# PROCESSOR_MEMORIES.net
KiCad netlist of a schematic drawn in Altium Designer
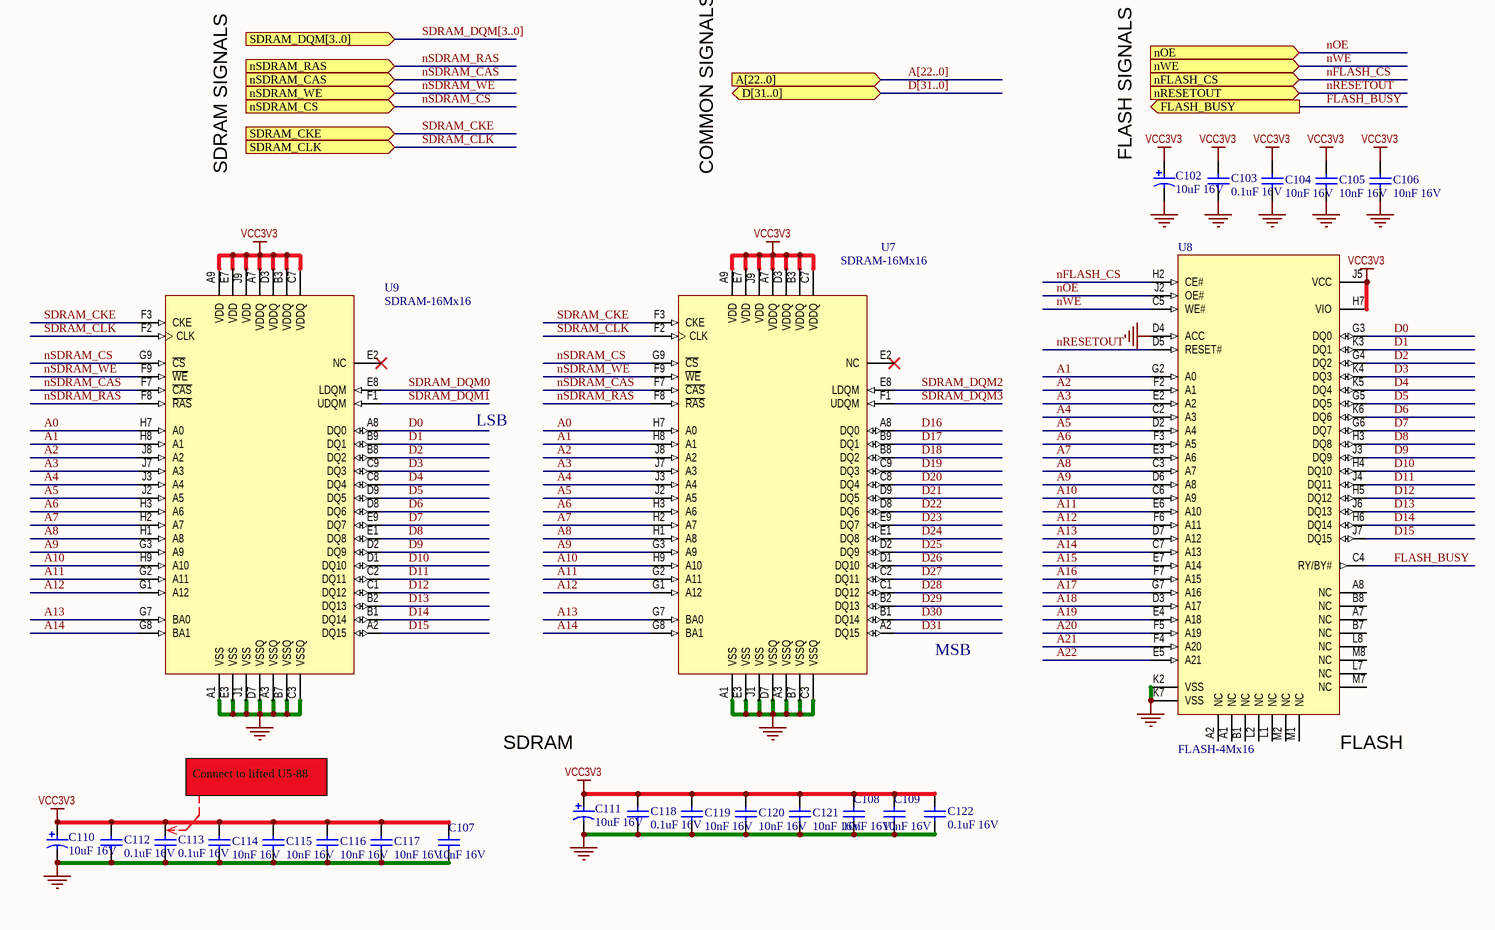
[diagram p0: PROCESSOR_MEMORIES.SchDoc]

(export (version "E")
  (design (tool "Eeschema 10.0.6"))
  (components
    (comp (ref "C102")
      (value "10uF 16V")
      (footprint "CAPC3528")
      (description "Polar Capacitor")
      (libsource (lib "Altium Design Library") (part "CAP-P"))
    )
    (comp (ref "C103")
      (value "0.1uF 16V")
      (footprint "CAPC1005")
      (description "Capacitor")
      (libsource (lib "Altium Design Library") (part "CAP-NP"))
    )
    (comp (ref "C104")
      (value "10nF 16V")
      (footprint "CAPC1005")
      (description "Capacitor")
      (libsource (lib "Altium Design Library") (part "CAP-NP"))
    )
    (comp (ref "C105")
      (value "10nF 16V")
      (footprint "CAPC1005")
      (description "Capacitor")
      (libsource (lib "Altium Design Library") (part "CAP-NP"))
    )
    (comp (ref "C106")
      (value "10nF 16V")
      (footprint "CAPC1005")
      (description "Capacitor")
      (libsource (lib "Altium Design Library") (part "CAP-NP"))
    )
    (comp (ref "C107")
      (value "10nF 16V")
      (footprint "CAPC1005")
      (description "Capacitor")
      (libsource (lib "Altium Design Library") (part "CAP-NP"))
    )
    (comp (ref "C108")
      (value "10nF 16V")
      (footprint "CAPC1005")
      (description "Capacitor")
      (libsource (lib "Altium Design Library") (part "CAP-NP"))
    )
    (comp (ref "C109")
      (value "10nF 16V")
      (footprint "CAPC1005")
      (description "Capacitor")
      (libsource (lib "Altium Design Library") (part "CAP-NP"))
    )
    (comp (ref "C110")
      (value "10uF 16V")
      (footprint "CAPC3528")
      (description "Polar Capacitor")
      (libsource (lib "Altium Design Library") (part "CAP-P"))
    )
    (comp (ref "C111")
      (value "10uF 16V")
      (footprint "CAPC3528")
      (description "Polar Capacitor")
      (libsource (lib "Altium Design Library") (part "CAP-P"))
    )
    (comp (ref "C112")
      (value "0.1uF 16V")
      (footprint "CAPC1005")
      (description "Capacitor")
      (libsource (lib "Altium Design Library") (part "CAP-NP"))
    )
    (comp (ref "C113")
      (value "0.1uF 16V")
      (footprint "CAPC1005")
      (description "Capacitor")
      (libsource (lib "Altium Design Library") (part "CAP-NP"))
    )
    (comp (ref "C114")
      (value "10nF 16V")
      (footprint "CAPC1005")
      (description "Capacitor")
      (libsource (lib "Altium Design Library") (part "CAP-NP"))
    )
    (comp (ref "C115")
      (value "10nF 16V")
      (footprint "CAPC1005")
      (description "Capacitor")
      (libsource (lib "Altium Design Library") (part "CAP-NP"))
    )
    (comp (ref "C116")
      (value "10nF 16V")
      (footprint "CAPC1005")
      (description "Capacitor")
      (libsource (lib "Altium Design Library") (part "CAP-NP"))
    )
    (comp (ref "C117")
      (value "10nF 16V")
      (footprint "CAPC1005")
      (description "Capacitor")
      (libsource (lib "Altium Design Library") (part "CAP-NP"))
    )
    (comp (ref "C118")
      (value "0.1uF 16V")
      (footprint "CAPC1005")
      (description "Capacitor")
      (libsource (lib "Altium Design Library") (part "CAP-NP"))
    )
    (comp (ref "C119")
      (value "10nF 16V")
      (footprint "CAPC1005")
      (description "Capacitor")
      (libsource (lib "Altium Design Library") (part "CAP-NP"))
    )
    (comp (ref "C120")
      (value "10nF 16V")
      (footprint "CAPC1005")
      (description "Capacitor")
      (libsource (lib "Altium Design Library") (part "CAP-NP"))
    )
    (comp (ref "C121")
      (value "10nF 16V")
      (footprint "CAPC1005")
      (description "Capacitor")
      (libsource (lib "Altium Design Library") (part "CAP-NP"))
    )
    (comp (ref "C122")
      (value "0.1uF 16V")
      (footprint "CAPC1005")
      (description "Capacitor")
      (libsource (lib "Altium Design Library") (part "CAP-NP"))
    )
    (comp (ref "U7")
      (value "SDRAM-16Mx16")
      (footprint "BGA80P9X6-54")
      (description "256Mb Synchronous High-Speed CMOS DRAM, 16Mb x 16Bit x 4 Banks, 54-Ball FPGA, Commercial")
      (libsource (lib "Altium Design Library") (part "MT48LC16M16A2FG"))
    )
    (comp (ref "U8")
      (value "FLASH-4Mx16")
      (footprint "BGA80P12X8-63")
      (libsource (lib "Altium Design Library") (part "AM29LV640DU90RWHI"))
    )
    (comp (ref "U9")
      (value "SDRAM-16Mx16")
      (footprint "BGA80P9X6-54")
      (description "256Mb Synchronous High-Speed CMOS DRAM, 16Mb x 16Bit x 4 Banks, 54-Ball FPGA, Commercial")
      (libsource (lib "Altium Design Library") (part "MT48LC16M16A2FG"))
    )
  )
  (nets
    (net (code "1") (name "/A0") (class "Default")
      (node (ref "U7") (pin "H7") (pinfunction "A0_H7") (pintype "input"))
      (node (ref "U9") (pin "H7") (pinfunction "A0_H7") (pintype "input"))
    )
    (net (code "2") (name "/A1") (class "Default")
      (node (ref "U7") (pin "H8") (pinfunction "A1_H8") (pintype "input"))
      (node (ref "U8") (pin "G2") (pinfunction "A0_G2") (pintype "input"))
      (node (ref "U9") (pin "H8") (pinfunction "A1_H8") (pintype "input"))
    )
    (net (code "3") (name "/A2") (class "Default")
      (node (ref "U7") (pin "J8") (pinfunction "A2_J8") (pintype "input"))
      (node (ref "U8") (pin "F2") (pinfunction "A1_F2") (pintype "input"))
      (node (ref "U9") (pin "J8") (pinfunction "A2_J8") (pintype "input"))
    )
    (net (code "4") (name "/A3") (class "Default")
      (node (ref "U7") (pin "J7") (pinfunction "A3_J7") (pintype "input"))
      (node (ref "U8") (pin "E2") (pinfunction "A2_E2") (pintype "input"))
      (node (ref "U9") (pin "J7") (pinfunction "A3_J7") (pintype "input"))
    )
    (net (code "5") (name "/A4") (class "Default")
      (node (ref "U7") (pin "J3") (pinfunction "A4_J3") (pintype "input"))
      (node (ref "U8") (pin "C2") (pinfunction "A3_C2") (pintype "input"))
      (node (ref "U9") (pin "J3") (pinfunction "A4_J3") (pintype "input"))
    )
    (net (code "6") (name "/A5") (class "Default")
      (node (ref "U7") (pin "J2") (pinfunction "A5_J2") (pintype "input"))
      (node (ref "U8") (pin "D2") (pinfunction "A4_D2") (pintype "input"))
      (node (ref "U9") (pin "J2") (pinfunction "A5_J2") (pintype "input"))
    )
    (net (code "7") (name "/A6") (class "Default")
      (node (ref "U7") (pin "H3") (pinfunction "A6_H3") (pintype "input"))
      (node (ref "U8") (pin "F3") (pinfunction "A5_F3") (pintype "input"))
      (node (ref "U9") (pin "H3") (pinfunction "A6_H3") (pintype "input"))
    )
    (net (code "8") (name "/A7") (class "Default")
      (node (ref "U7") (pin "H2") (pinfunction "A7_H2") (pintype "input"))
      (node (ref "U8") (pin "E3") (pinfunction "A6_E3") (pintype "input"))
      (node (ref "U9") (pin "H2") (pinfunction "A7_H2") (pintype "input"))
    )
    (net (code "9") (name "/A8") (class "Default")
      (node (ref "U7") (pin "H1") (pinfunction "A8_H1") (pintype "input"))
      (node (ref "U8") (pin "C3") (pinfunction "A7_C3") (pintype "input"))
      (node (ref "U9") (pin "H1") (pinfunction "A8_H1") (pintype "input"))
    )
    (net (code "10") (name "/A9") (class "Default")
      (node (ref "U7") (pin "G3") (pinfunction "A9_G3") (pintype "input"))
      (node (ref "U8") (pin "D6") (pinfunction "A8_D6") (pintype "input"))
      (node (ref "U9") (pin "G3") (pinfunction "A9_G3") (pintype "input"))
    )
    (net (code "11") (name "/A10") (class "Default")
      (node (ref "U7") (pin "H9") (pinfunction "A10_H9") (pintype "input"))
      (node (ref "U8") (pin "C6") (pinfunction "A9_C6") (pintype "input"))
      (node (ref "U9") (pin "H9") (pinfunction "A10_H9") (pintype "input"))
    )
    (net (code "12") (name "/A11") (class "Default")
      (node (ref "U7") (pin "G2") (pinfunction "A11_G2") (pintype "input"))
      (node (ref "U8") (pin "E6") (pinfunction "A10_E6") (pintype "input"))
      (node (ref "U9") (pin "G2") (pinfunction "A11_G2") (pintype "input"))
    )
    (net (code "13") (name "/A12") (class "Default")
      (node (ref "U7") (pin "G1") (pinfunction "A12_G1") (pintype "input"))
      (node (ref "U8") (pin "F6") (pinfunction "A11_F6") (pintype "input"))
      (node (ref "U9") (pin "G1") (pinfunction "A12_G1") (pintype "input"))
    )
    (net (code "14") (name "/A13") (class "Default")
      (node (ref "U7") (pin "G7") (pinfunction "BA0_G7") (pintype "input"))
      (node (ref "U8") (pin "D7") (pinfunction "A12_D7") (pintype "input"))
      (node (ref "U9") (pin "G7") (pinfunction "BA0_G7") (pintype "input"))
    )
    (net (code "15") (name "/A14") (class "Default")
      (node (ref "U7") (pin "G8") (pinfunction "BA1_G8") (pintype "input"))
      (node (ref "U8") (pin "C7") (pinfunction "A13_C7") (pintype "input"))
      (node (ref "U9") (pin "G8") (pinfunction "BA1_G8") (pintype "input"))
    )
    (net (code "16") (name "/A15") (class "Default")
      (node (ref "U8") (pin "E7") (pinfunction "A14_E7") (pintype "input"))
    )
    (net (code "17") (name "/A16") (class "Default")
      (node (ref "U8") (pin "F7") (pinfunction "A15_F7") (pintype "input"))
    )
    (net (code "18") (name "/A17") (class "Default")
      (node (ref "U8") (pin "G7") (pinfunction "A16_G7") (pintype "input"))
    )
    (net (code "19") (name "/A18") (class "Default")
      (node (ref "U8") (pin "D3") (pinfunction "A17_D3") (pintype "input"))
    )
    (net (code "20") (name "/A19") (class "Default")
      (node (ref "U8") (pin "E4") (pinfunction "A18_E4") (pintype "input"))
    )
    (net (code "21") (name "/A20") (class "Default")
      (node (ref "U8") (pin "F5") (pinfunction "A19_F5") (pintype "input"))
    )
    (net (code "22") (name "/A21") (class "Default")
      (node (ref "U8") (pin "F4") (pinfunction "A20_F4") (pintype "input"))
    )
    (net (code "23") (name "/A22") (class "Default")
      (node (ref "U8") (pin "E5") (pinfunction "A21_E5") (pintype "input"))
    )
    (net (code "25") (name "/D0") (class "Default")
      (node (ref "U8") (pin "G3") (pinfunction "DQ0_G3") (pintype "bidirectional"))
      (node (ref "U9") (pin "A8") (pinfunction "DQ0_A8") (pintype "bidirectional"))
    )
    (net (code "26") (name "/D1") (class "Default")
      (node (ref "U8") (pin "K3") (pinfunction "DQ1_K3") (pintype "bidirectional"))
      (node (ref "U9") (pin "B9") (pinfunction "DQ1_B9") (pintype "bidirectional"))
    )
    (net (code "27") (name "/D2") (class "Default")
      (node (ref "U8") (pin "G4") (pinfunction "DQ2_G4") (pintype "bidirectional"))
      (node (ref "U9") (pin "B8") (pinfunction "DQ2_B8") (pintype "bidirectional"))
    )
    (net (code "28") (name "/D3") (class "Default")
      (node (ref "U8") (pin "K4") (pinfunction "DQ3_K4") (pintype "bidirectional"))
      (node (ref "U9") (pin "C9") (pinfunction "DQ3_C9") (pintype "bidirectional"))
    )
    (net (code "29") (name "/D4") (class "Default")
      (node (ref "U8") (pin "K5") (pinfunction "DQ4_K5") (pintype "bidirectional"))
      (node (ref "U9") (pin "C8") (pinfunction "DQ4_C8") (pintype "bidirectional"))
    )
    (net (code "30") (name "/D5") (class "Default")
      (node (ref "U8") (pin "G5") (pinfunction "DQ5_G5") (pintype "bidirectional"))
      (node (ref "U9") (pin "D9") (pinfunction "DQ5_D9") (pintype "bidirectional"))
    )
    (net (code "31") (name "/D6") (class "Default")
      (node (ref "U8") (pin "K6") (pinfunction "DQ6_K6") (pintype "bidirectional"))
      (node (ref "U9") (pin "D8") (pinfunction "DQ6_D8") (pintype "bidirectional"))
    )
    (net (code "32") (name "/D7") (class "Default")
      (node (ref "U8") (pin "G6") (pinfunction "DQ7_G6") (pintype "bidirectional"))
      (node (ref "U9") (pin "E9") (pinfunction "DQ7_E9") (pintype "bidirectional"))
    )
    (net (code "33") (name "/D8") (class "Default")
      (node (ref "U8") (pin "H3") (pinfunction "DQ8_H3") (pintype "bidirectional"))
      (node (ref "U9") (pin "E1") (pinfunction "DQ8_E1") (pintype "bidirectional"))
    )
    (net (code "34") (name "/D9") (class "Default")
      (node (ref "U8") (pin "J3") (pinfunction "DQ9_J3") (pintype "bidirectional"))
      (node (ref "U9") (pin "D2") (pinfunction "DQ9_D2") (pintype "bidirectional"))
    )
    (net (code "35") (name "/D10") (class "Default")
      (node (ref "U8") (pin "H4") (pinfunction "DQ10_H4") (pintype "bidirectional"))
      (node (ref "U9") (pin "D1") (pinfunction "DQ10_D1") (pintype "bidirectional"))
    )
    (net (code "36") (name "/D11") (class "Default")
      (node (ref "U8") (pin "J4") (pinfunction "DQ11_J4") (pintype "bidirectional"))
      (node (ref "U9") (pin "C2") (pinfunction "DQ11_C2") (pintype "bidirectional"))
    )
    (net (code "37") (name "/D12") (class "Default")
      (node (ref "U8") (pin "H5") (pinfunction "DQ12_H5") (pintype "bidirectional"))
      (node (ref "U9") (pin "C1") (pinfunction "DQ12_C1") (pintype "bidirectional"))
    )
    (net (code "38") (name "/D13") (class "Default")
      (node (ref "U8") (pin "J6") (pinfunction "DQ13_J6") (pintype "bidirectional"))
      (node (ref "U9") (pin "B2") (pinfunction "DQ13_B2") (pintype "bidirectional"))
    )
    (net (code "39") (name "/D14") (class "Default")
      (node (ref "U8") (pin "H6") (pinfunction "DQ14_H6") (pintype "bidirectional"))
      (node (ref "U9") (pin "B1") (pinfunction "DQ14_B1") (pintype "bidirectional"))
    )
    (net (code "40") (name "/D15") (class "Default")
      (node (ref "U8") (pin "J7") (pinfunction "DQ15_J7") (pintype "bidirectional"))
      (node (ref "U9") (pin "A2") (pinfunction "DQ15_A2") (pintype "bidirectional"))
    )
    (net (code "41") (name "/D16") (class "Default")
      (node (ref "U7") (pin "A8") (pinfunction "DQ0_A8") (pintype "bidirectional"))
    )
    (net (code "42") (name "/D17") (class "Default")
      (node (ref "U7") (pin "B9") (pinfunction "DQ1_B9") (pintype "bidirectional"))
    )
    (net (code "43") (name "/D18") (class "Default")
      (node (ref "U7") (pin "B8") (pinfunction "DQ2_B8") (pintype "bidirectional"))
    )
    (net (code "44") (name "/D19") (class "Default")
      (node (ref "U7") (pin "C9") (pinfunction "DQ3_C9") (pintype "bidirectional"))
    )
    (net (code "45") (name "/D20") (class "Default")
      (node (ref "U7") (pin "C8") (pinfunction "DQ4_C8") (pintype "bidirectional"))
    )
    (net (code "46") (name "/D21") (class "Default")
      (node (ref "U7") (pin "D9") (pinfunction "DQ5_D9") (pintype "bidirectional"))
    )
    (net (code "47") (name "/D22") (class "Default")
      (node (ref "U7") (pin "D8") (pinfunction "DQ6_D8") (pintype "bidirectional"))
    )
    (net (code "48") (name "/D23") (class "Default")
      (node (ref "U7") (pin "E9") (pinfunction "DQ7_E9") (pintype "bidirectional"))
    )
    (net (code "49") (name "/D24") (class "Default")
      (node (ref "U7") (pin "E1") (pinfunction "DQ8_E1") (pintype "bidirectional"))
    )
    (net (code "50") (name "/D25") (class "Default")
      (node (ref "U7") (pin "D2") (pinfunction "DQ9_D2") (pintype "bidirectional"))
    )
    (net (code "51") (name "/D26") (class "Default")
      (node (ref "U7") (pin "D1") (pinfunction "DQ10_D1") (pintype "bidirectional"))
    )
    (net (code "52") (name "/D27") (class "Default")
      (node (ref "U7") (pin "C2") (pinfunction "DQ11_C2") (pintype "bidirectional"))
    )
    (net (code "53") (name "/D28") (class "Default")
      (node (ref "U7") (pin "C1") (pinfunction "DQ12_C1") (pintype "bidirectional"))
    )
    (net (code "54") (name "/D29") (class "Default")
      (node (ref "U7") (pin "B2") (pinfunction "DQ13_B2") (pintype "bidirectional"))
    )
    (net (code "55") (name "/D30") (class "Default")
      (node (ref "U7") (pin "B1") (pinfunction "DQ14_B1") (pintype "bidirectional"))
    )
    (net (code "56") (name "/D31") (class "Default")
      (node (ref "U7") (pin "A2") (pinfunction "DQ15_A2") (pintype "bidirectional"))
    )
    (net (code "58") (name "/FLASH_BUSY") (class "Default")
      (node (ref "U8") (pin "C4") (pinfunction "RY/BY#_C4") (pintype "output"))
    )
    (net (code "59") (name "/SDRAM_CKE") (class "Default")
      (node (ref "U7") (pin "F3") (pinfunction "CKE_F3") (pintype "input"))
      (node (ref "U9") (pin "F3") (pinfunction "CKE_F3") (pintype "input"))
    )
    (net (code "60") (name "/SDRAM_CLK") (class "Default")
      (node (ref "U7") (pin "F2") (pinfunction "CLK_F2") (pintype "input"))
      (node (ref "U9") (pin "F2") (pinfunction "CLK_F2") (pintype "input"))
    )
    (net (code "61") (name "/SDRAM_DQM0") (class "Default")
      (node (ref "U9") (pin "E8") (pinfunction "LDQM_E8") (pintype "input"))
    )
    (net (code "62") (name "/SDRAM_DQM1") (class "Default")
      (node (ref "U9") (pin "F1") (pinfunction "UDQM_F1") (pintype "input"))
    )
    (net (code "63") (name "/SDRAM_DQM2") (class "Default")
      (node (ref "U7") (pin "E8") (pinfunction "LDQM_E8") (pintype "input"))
    )
    (net (code "64") (name "/SDRAM_DQM3") (class "Default")
      (node (ref "U7") (pin "F1") (pinfunction "UDQM_F1") (pintype "input"))
    )
    (net (code "66") (name "/nFLASH_CS") (class "Default")
      (node (ref "U8") (pin "H2") (pinfunction "CE#_H2") (pintype "input"))
    )
    (net (code "67") (name "/nOE") (class "Default")
      (node (ref "U8") (pin "J2") (pinfunction "OE#_J2") (pintype "input"))
    )
    (net (code "68") (name "/nRESETOUT") (class "Default")
      (node (ref "U8") (pin "D5") (pinfunction "RESET#_D5") (pintype "input"))
    )
    (net (code "69") (name "/nSDRAM_CAS") (class "Default")
      (node (ref "U7") (pin "F7") (pinfunction "~{CAS}_F7") (pintype "input"))
      (node (ref "U9") (pin "F7") (pinfunction "~{CAS}_F7") (pintype "input"))
    )
    (net (code "70") (name "/nSDRAM_CS") (class "Default")
      (node (ref "U7") (pin "G9") (pinfunction "~{CS}_G9") (pintype "input"))
      (node (ref "U9") (pin "G9") (pinfunction "~{CS}_G9") (pintype "input"))
    )
    (net (code "71") (name "/nSDRAM_RAS") (class "Default")
      (node (ref "U7") (pin "F8") (pinfunction "~{RAS}_F8") (pintype "input"))
      (node (ref "U9") (pin "F8") (pinfunction "~{RAS}_F8") (pintype "input"))
    )
    (net (code "72") (name "/nSDRAM_WE") (class "Default")
      (node (ref "U7") (pin "F9") (pinfunction "~{WE}_F9") (pintype "input"))
      (node (ref "U9") (pin "F9") (pinfunction "~{WE}_F9") (pintype "input"))
    )
    (net (code "73") (name "/nWE") (class "Default")
      (node (ref "U8") (pin "C5") (pinfunction "WE#_C5") (pintype "input"))
    )
    (net (code "74") (name "GND") (class "Default")
      (node (ref "C102") (pin "2") (pinfunction "2_2") (pintype "passive"))
      (node (ref "C103") (pin "2") (pinfunction "2_2") (pintype "passive"))
      (node (ref "C104") (pin "2") (pinfunction "2_2") (pintype "passive"))
      (node (ref "C105") (pin "2") (pinfunction "2_2") (pintype "passive"))
      (node (ref "C106") (pin "2") (pinfunction "2_2") (pintype "passive"))
      (node (ref "C107") (pin "2") (pinfunction "2_2") (pintype "passive"))
      (node (ref "C108") (pin "2") (pinfunction "2_2") (pintype "passive"))
      (node (ref "C109") (pin "2") (pinfunction "2_2") (pintype "passive"))
      (node (ref "C110") (pin "2") (pinfunction "2_2") (pintype "passive"))
      (node (ref "C111") (pin "2") (pinfunction "2_2") (pintype "passive"))
      (node (ref "C112") (pin "2") (pinfunction "2_2") (pintype "passive"))
      (node (ref "C113") (pin "2") (pinfunction "2_2") (pintype "passive"))
      (node (ref "C114") (pin "2") (pinfunction "2_2") (pintype "passive"))
      (node (ref "C115") (pin "2") (pinfunction "2_2") (pintype "passive"))
      (node (ref "C116") (pin "2") (pinfunction "2_2") (pintype "passive"))
      (node (ref "C117") (pin "2") (pinfunction "2_2") (pintype "passive"))
      (node (ref "C118") (pin "2") (pinfunction "2_2") (pintype "passive"))
      (node (ref "C119") (pin "2") (pinfunction "2_2") (pintype "passive"))
      (node (ref "C120") (pin "2") (pinfunction "2_2") (pintype "passive"))
      (node (ref "C121") (pin "2") (pinfunction "2_2") (pintype "passive"))
      (node (ref "C122") (pin "2") (pinfunction "2_2") (pintype "passive"))
      (node (ref "U7") (pin "A1") (pinfunction "VSS_A1") (pintype "power_in"))
      (node (ref "U7") (pin "A3") (pinfunction "VSSQ_A3") (pintype "power_in"))
      (node (ref "U7") (pin "B7") (pinfunction "VSSQ_B7") (pintype "power_in"))
      (node (ref "U7") (pin "C3") (pinfunction "VSSQ_C3") (pintype "power_in"))
      (node (ref "U7") (pin "D7") (pinfunction "VSSQ_D7") (pintype "power_in"))
      (node (ref "U7") (pin "E3") (pinfunction "VSS_E3") (pintype "power_in"))
      (node (ref "U7") (pin "J1") (pinfunction "VSS_J1") (pintype "power_in"))
      (node (ref "U8") (pin "D4") (pinfunction "ACC_D4") (pintype "input"))
      (node (ref "U8") (pin "K2") (pinfunction "VSS_K2") (pintype "power_in"))
      (node (ref "U8") (pin "K7") (pinfunction "VSS_K7") (pintype "power_in"))
      (node (ref "U9") (pin "A1") (pinfunction "VSS_A1") (pintype "power_in"))
      (node (ref "U9") (pin "A3") (pinfunction "VSSQ_A3") (pintype "power_in"))
      (node (ref "U9") (pin "B7") (pinfunction "VSSQ_B7") (pintype "power_in"))
      (node (ref "U9") (pin "C3") (pinfunction "VSSQ_C3") (pintype "power_in"))
      (node (ref "U9") (pin "D7") (pinfunction "VSSQ_D7") (pintype "power_in"))
      (node (ref "U9") (pin "E3") (pinfunction "VSS_E3") (pintype "power_in"))
      (node (ref "U9") (pin "J1") (pinfunction "VSS_J1") (pintype "power_in"))
    )
    (net (code "75") (name "VCC3V3") (class "Default")
      (node (ref "C102") (pin "1") (pinfunction "1_1") (pintype "passive"))
      (node (ref "C103") (pin "1") (pinfunction "1_1") (pintype "passive"))
      (node (ref "C104") (pin "1") (pinfunction "1_1") (pintype "passive"))
      (node (ref "C105") (pin "1") (pinfunction "1_1") (pintype "passive"))
      (node (ref "C106") (pin "1") (pinfunction "1_1") (pintype "passive"))
      (node (ref "C107") (pin "1") (pinfunction "1_1") (pintype "passive"))
      (node (ref "C108") (pin "1") (pinfunction "1_1") (pintype "passive"))
      (node (ref "C109") (pin "1") (pinfunction "1_1") (pintype "passive"))
      (node (ref "C110") (pin "1") (pinfunction "1_1") (pintype "passive"))
      (node (ref "C111") (pin "1") (pinfunction "1_1") (pintype "passive"))
      (node (ref "C112") (pin "1") (pinfunction "1_1") (pintype "passive"))
      (node (ref "C113") (pin "1") (pinfunction "1_1") (pintype "passive"))
      (node (ref "C114") (pin "1") (pinfunction "1_1") (pintype "passive"))
      (node (ref "C115") (pin "1") (pinfunction "1_1") (pintype "passive"))
      (node (ref "C116") (pin "1") (pinfunction "1_1") (pintype "passive"))
      (node (ref "C117") (pin "1") (pinfunction "1_1") (pintype "passive"))
      (node (ref "C118") (pin "1") (pinfunction "1_1") (pintype "passive"))
      (node (ref "C119") (pin "1") (pinfunction "1_1") (pintype "passive"))
      (node (ref "C120") (pin "1") (pinfunction "1_1") (pintype "passive"))
      (node (ref "C121") (pin "1") (pinfunction "1_1") (pintype "passive"))
      (node (ref "C122") (pin "1") (pinfunction "1_1") (pintype "passive"))
      (node (ref "U7") (pin "A7") (pinfunction "VDDQ_A7") (pintype "power_in"))
      (node (ref "U7") (pin "A9") (pinfunction "VDD_A9") (pintype "power_in"))
      (node (ref "U7") (pin "B3") (pinfunction "VDDQ_B3") (pintype "power_in"))
      (node (ref "U7") (pin "C7") (pinfunction "VDDQ_C7") (pintype "power_in"))
      (node (ref "U7") (pin "D3") (pinfunction "VDDQ_D3") (pintype "power_in"))
      (node (ref "U7") (pin "E7") (pinfunction "VDD_E7") (pintype "power_in"))
      (node (ref "U7") (pin "J9") (pinfunction "VDD_J9") (pintype "power_in"))
      (node (ref "U8") (pin "H7") (pinfunction "VIO_H7") (pintype "power_in"))
      (node (ref "U8") (pin "J5") (pinfunction "VCC_J5") (pintype "power_in"))
      (node (ref "U9") (pin "A7") (pinfunction "VDDQ_A7") (pintype "power_in"))
      (node (ref "U9") (pin "A9") (pinfunction "VDD_A9") (pintype "power_in"))
      (node (ref "U9") (pin "B3") (pinfunction "VDDQ_B3") (pintype "power_in"))
      (node (ref "U9") (pin "C7") (pinfunction "VDDQ_C7") (pintype "power_in"))
      (node (ref "U9") (pin "D3") (pinfunction "VDDQ_D3") (pintype "power_in"))
      (node (ref "U9") (pin "E7") (pinfunction "VDD_E7") (pintype "power_in"))
      (node (ref "U9") (pin "J9") (pinfunction "VDD_J9") (pintype "power_in"))
    )
    (net (code "76") (name "unconnected-(U7-NC-PadE2)") (class "Default")
      (node (ref "U7") (pin "E2") (pinfunction "NC_E2") (pintype "passive+no_connect"))
    )
    (net (code "77") (name "unconnected-(U8-NC-PadA1)") (class "Default")
      (node (ref "U8") (pin "A1") (pinfunction "NC_A1") (pintype "passive"))
    )
    (net (code "78") (name "unconnected-(U8-NC-PadA2)") (class "Default")
      (node (ref "U8") (pin "A2") (pinfunction "NC_A2") (pintype "passive"))
    )
    (net (code "79") (name "unconnected-(U8-NC-PadA7)") (class "Default")
      (node (ref "U8") (pin "A7") (pinfunction "NC_A7") (pintype "passive"))
    )
    (net (code "80") (name "unconnected-(U8-NC-PadA8)") (class "Default")
      (node (ref "U8") (pin "A8") (pinfunction "NC_A8") (pintype "passive"))
    )
    (net (code "81") (name "unconnected-(U8-NC-PadB1)") (class "Default")
      (node (ref "U8") (pin "B1") (pinfunction "NC_B1") (pintype "passive"))
    )
    (net (code "82") (name "unconnected-(U8-NC-PadB7)") (class "Default")
      (node (ref "U8") (pin "B7") (pinfunction "NC_B7") (pintype "passive"))
    )
    (net (code "83") (name "unconnected-(U8-NC-PadB8)") (class "Default")
      (node (ref "U8") (pin "B8") (pinfunction "NC_B8") (pintype "passive"))
    )
    (net (code "84") (name "unconnected-(U8-NC-PadL1)") (class "Default")
      (node (ref "U8") (pin "L1") (pinfunction "NC_L1") (pintype "passive"))
    )
    (net (code "85") (name "unconnected-(U8-NC-PadL2)") (class "Default")
      (node (ref "U8") (pin "L2") (pinfunction "NC_L2") (pintype "passive"))
    )
    (net (code "86") (name "unconnected-(U8-NC-PadL7)") (class "Default")
      (node (ref "U8") (pin "L7") (pinfunction "NC_L7") (pintype "passive"))
    )
    (net (code "87") (name "unconnected-(U8-NC-PadL8)") (class "Default")
      (node (ref "U8") (pin "L8") (pinfunction "NC_L8") (pintype "passive"))
    )
    (net (code "88") (name "unconnected-(U8-NC-PadM1)") (class "Default")
      (node (ref "U8") (pin "M1") (pinfunction "NC_M1") (pintype "passive"))
    )
    (net (code "89") (name "unconnected-(U8-NC-PadM2)") (class "Default")
      (node (ref "U8") (pin "M2") (pinfunction "NC_M2") (pintype "passive"))
    )
    (net (code "90") (name "unconnected-(U8-NC-PadM7)") (class "Default")
      (node (ref "U8") (pin "M7") (pinfunction "NC_M7") (pintype "passive"))
    )
    (net (code "91") (name "unconnected-(U8-NC-PadM8)") (class "Default")
      (node (ref "U8") (pin "M8") (pinfunction "NC_M8") (pintype "passive"))
    )
    (net (code "92") (name "unconnected-(U9-NC-PadE2)") (class "Default")
      (node (ref "U9") (pin "E2") (pinfunction "NC_E2") (pintype "passive+no_connect"))
    )
  )
)
